# M14_Potis.net
KiCad netlist of a schematic drawn in EAGLE
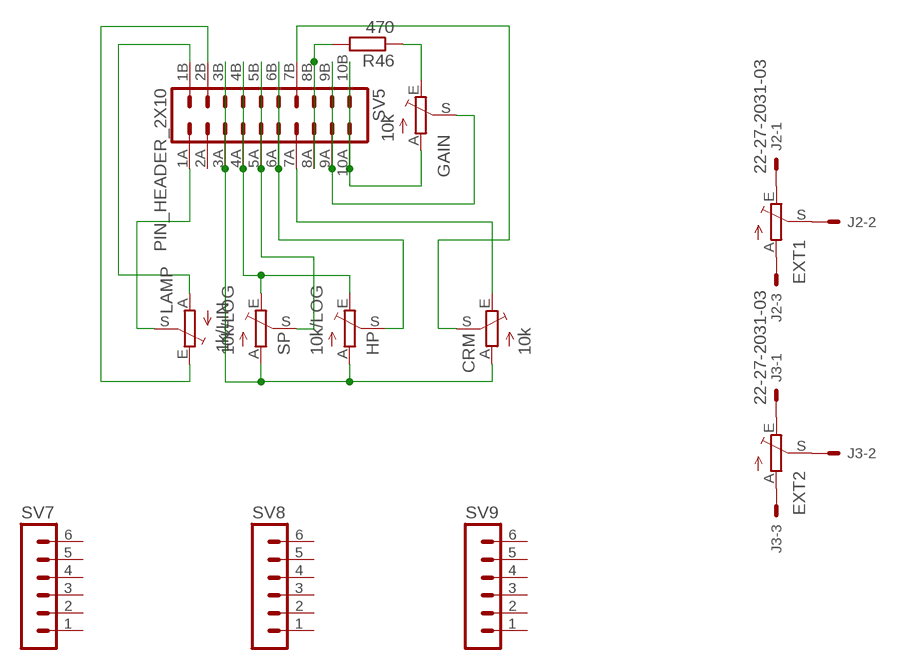
[diagram p0: schematic, sheet 1]

(export (version "E")
  (design (tool "Eeschema 10.0.6"))
  (components
    (comp (ref "CRM")
      (value "10k")
      (footprint "eagle-import:PT-10")
      (libsource (lib "eagle-import") (part "TRIM_EU-PT10"))
    )
    (comp (ref "EXT1")
      (value "TRIM_EU-PT10")
      (footprint "eagle-import:PT-10")
      (libsource (lib "eagle-import") (part "TRIM_EU-PT10"))
    )
    (comp (ref "EXT2")
      (value "TRIM_EU-PT10")
      (footprint "eagle-import:PT-10")
      (libsource (lib "eagle-import") (part "TRIM_EU-PT10"))
    )
    (comp (ref "GAIN")
      (value "10k")
      (footprint "eagle-import:PT-10")
      (libsource (lib "eagle-import") (part "TRIM_EU-PT10"))
    )
    (comp (ref "HP")
      (value "10k/LOG")
      (footprint "eagle-import:POT_NAR")
      (libsource (lib "eagle-import") (part "TRIM_EU-POT_WHOLE"))
    )
    (comp (ref "J2")
      (value "22-27-2031-03")
      (footprint "eagle-import:6410-03")
      (libsource (lib "eagle-import") (part "22-?-0327-2031"))
    )
    (comp (ref "J3")
      (value "22-27-2031-03")
      (footprint "eagle-import:6410-03")
      (libsource (lib "eagle-import") (part "22-?-0327-2031"))
    )
    (comp (ref "LAMP")
      (value "1k/LIN")
      (footprint "eagle-import:POT_NAR")
      (libsource (lib "eagle-import") (part "TRIM_EU-POT_WHOLE"))
    )
    (comp (ref "R46")
      (value "470")
      (footprint "eagle-import:R0805")
      (libsource (lib "eagle-import") (part "R-EU_R0805"))
    )
    (comp (ref "SP")
      (value "10k/LOG")
      (footprint "eagle-import:POT_NAR")
      (libsource (lib "eagle-import") (part "TRIM_EU-POT_WHOLE"))
    )
    (comp (ref "SV5")
      (value "PIN_HEADER_2X10")
      (footprint "eagle-import:PIN_HEADER_2X10SMD")
      (libsource (lib "eagle-import") (part "PIN_HEADER_2X10"))
    )
    (comp (ref "SV7")
      (value "MA06-1")
      (footprint "eagle-import:MA06-1")
      (libsource (lib "eagle-import") (part "MA06-1"))
    )
    (comp (ref "SV8")
      (value "MA06-1")
      (footprint "eagle-import:MA06-1")
      (libsource (lib "eagle-import") (part "MA06-1"))
    )
    (comp (ref "SV9")
      (value "MA06-1")
      (footprint "eagle-import:MA06-1")
      (libsource (lib "eagle-import") (part "MA06-1"))
    )
  )
  (nets
    (net (code "1") (name "Net-(GAIN-PadE)") (class "Default")
      (node (ref "GAIN") (pin "E") (pinfunction "E_E") (pintype "passive"))
      (node (ref "R46") (pin "1") (pinfunction "1_1") (pintype "passive"))
    )
    (net (code "2") (name "Net-(J2A-S)") (class "Default")
      (node (ref "EXT1") (pin "E") (pinfunction "E_E") (pintype "passive"))
      (node (ref "J2") (pin "1") (pinfunction "S_1") (pintype "passive"))
    )
    (net (code "3") (name "Net-(J2B-S)") (class "Default")
      (node (ref "EXT1") (pin "S") (pinfunction "S_S") (pintype "passive"))
      (node (ref "J2") (pin "2") (pinfunction "S_2") (pintype "passive"))
    )
    (net (code "4") (name "Net-(J2C-S)") (class "Default")
      (node (ref "EXT1") (pin "A") (pinfunction "A_A") (pintype "passive"))
      (node (ref "J2") (pin "3") (pinfunction "S_3") (pintype "passive"))
    )
    (net (code "5") (name "Net-(J3A-S)") (class "Default")
      (node (ref "EXT2") (pin "E") (pinfunction "E_E") (pintype "passive"))
      (node (ref "J3") (pin "1") (pinfunction "S_1") (pintype "passive"))
    )
    (net (code "6") (name "Net-(J3B-S)") (class "Default")
      (node (ref "EXT2") (pin "S") (pinfunction "S_S") (pintype "passive"))
      (node (ref "J3") (pin "2") (pinfunction "S_2") (pintype "passive"))
    )
    (net (code "7") (name "Net-(J3C-S)") (class "Default")
      (node (ref "EXT2") (pin "A") (pinfunction "A_A") (pintype "passive"))
      (node (ref "J3") (pin "3") (pinfunction "S_3") (pintype "passive"))
    )
    (net (code "8") (name "Net-(SV5-1)") (class "Default")
      (node (ref "LAMP") (pin "S") (pinfunction "S_S") (pintype "passive"))
      (node (ref "SV5") (pin "1A") (pinfunction "1_1A") (pintype "passive"))
    )
    (net (code "9") (name "Net-(SV5-2)") (class "Default")
      (node (ref "LAMP") (pin "A") (pinfunction "A_A") (pintype "passive"))
      (node (ref "SV5") (pin "1B") (pinfunction "2_1B") (pintype "passive"))
    )
    (net (code "10") (name "Net-(SV5-4)") (class "Default")
      (node (ref "LAMP") (pin "E") (pinfunction "E_E") (pintype "passive"))
      (node (ref "SV5") (pin "2B") (pinfunction "4_2B") (pintype "passive"))
    )
    (net (code "11") (name "Net-(SV5-5)") (class "Default")
      (node (ref "CRM") (pin "A") (pinfunction "A_A") (pintype "passive"))
      (node (ref "HP") (pin "A") (pinfunction "A_A") (pintype "passive"))
      (node (ref "SP") (pin "A") (pinfunction "A_A") (pintype "passive"))
      (node (ref "SV5") (pin "3A") (pinfunction "5_3A") (pintype "passive"))
      (node (ref "SV5") (pin "3B") (pinfunction "6_3B") (pintype "passive"))
    )
    (net (code "12") (name "Net-(SV5-7)") (class "Default")
      (node (ref "HP") (pin "E") (pinfunction "E_E") (pintype "passive"))
      (node (ref "SP") (pin "E") (pinfunction "E_E") (pintype "passive"))
      (node (ref "SV5") (pin "4A") (pinfunction "7_4A") (pintype "passive"))
      (node (ref "SV5") (pin "4B") (pinfunction "8_4B") (pintype "passive"))
    )
    (net (code "13") (name "Net-(SV5-10)") (class "Default")
      (node (ref "SP") (pin "S") (pinfunction "S_S") (pintype "passive"))
      (node (ref "SV5") (pin "5A") (pinfunction "9_5A") (pintype "passive"))
      (node (ref "SV5") (pin "5B") (pinfunction "10_5B") (pintype "passive"))
    )
    (net (code "14") (name "Net-(SV5-11)") (class "Default")
      (node (ref "HP") (pin "S") (pinfunction "S_S") (pintype "passive"))
      (node (ref "SV5") (pin "6A") (pinfunction "11_6A") (pintype "passive"))
      (node (ref "SV5") (pin "6B") (pinfunction "12_6B") (pintype "passive"))
    )
    (net (code "15") (name "Net-(SV5-13)") (class "Default")
      (node (ref "CRM") (pin "E") (pinfunction "E_E") (pintype "passive"))
      (node (ref "SV5") (pin "7A") (pinfunction "13_7A") (pintype "passive"))
    )
    (net (code "16") (name "Net-(SV5-14)") (class "Default")
      (node (ref "CRM") (pin "S") (pinfunction "S_S") (pintype "passive"))
      (node (ref "SV5") (pin "7B") (pinfunction "14_7B") (pintype "passive"))
    )
    (net (code "17") (name "Net-(SV5-15)") (class "Default")
      (node (ref "R46") (pin "2") (pinfunction "2_2") (pintype "passive"))
      (node (ref "SV5") (pin "8A") (pinfunction "15_8A") (pintype "passive"))
      (node (ref "SV5") (pin "8B") (pinfunction "16_8B") (pintype "passive"))
    )
    (net (code "18") (name "Net-(SV5-17)") (class "Default")
      (node (ref "GAIN") (pin "S") (pinfunction "S_S") (pintype "passive"))
      (node (ref "SV5") (pin "9A") (pinfunction "17_9A") (pintype "passive"))
      (node (ref "SV5") (pin "9B") (pinfunction "18_9B") (pintype "passive"))
    )
    (net (code "19") (name "Net-(SV5-19)") (class "Default")
      (node (ref "GAIN") (pin "A") (pinfunction "A_A") (pintype "passive"))
      (node (ref "SV5") (pin "10A") (pinfunction "19_10A") (pintype "passive"))
      (node (ref "SV5") (pin "10B") (pinfunction "20_10B") (pintype "passive"))
    )
    (net (code "20") (name "unconnected-(SV5-3-Pad2A)") (class "Default")
      (node (ref "SV5") (pin "2A") (pinfunction "3_2A") (pintype "passive"))
    )
    (net (code "21") (name "unconnected-(SV7-Pad1)") (class "Default")
      (node (ref "SV7") (pin "1") (pinfunction "1_1") (pintype "passive"))
    )
    (net (code "22") (name "unconnected-(SV7-Pad2)") (class "Default")
      (node (ref "SV7") (pin "2") (pinfunction "2_2") (pintype "passive"))
    )
    (net (code "23") (name "unconnected-(SV7-Pad3)") (class "Default")
      (node (ref "SV7") (pin "3") (pinfunction "3_3") (pintype "passive"))
    )
    (net (code "24") (name "unconnected-(SV7-Pad4)") (class "Default")
      (node (ref "SV7") (pin "4") (pinfunction "4_4") (pintype "passive"))
    )
    (net (code "25") (name "unconnected-(SV7-Pad5)") (class "Default")
      (node (ref "SV7") (pin "5") (pinfunction "5_5") (pintype "passive"))
    )
    (net (code "26") (name "unconnected-(SV7-Pad6)") (class "Default")
      (node (ref "SV7") (pin "6") (pinfunction "6_6") (pintype "passive"))
    )
    (net (code "27") (name "unconnected-(SV8-Pad1)") (class "Default")
      (node (ref "SV8") (pin "1") (pinfunction "1_1") (pintype "passive"))
    )
    (net (code "28") (name "unconnected-(SV8-Pad2)") (class "Default")
      (node (ref "SV8") (pin "2") (pinfunction "2_2") (pintype "passive"))
    )
    (net (code "29") (name "unconnected-(SV8-Pad3)") (class "Default")
      (node (ref "SV8") (pin "3") (pinfunction "3_3") (pintype "passive"))
    )
    (net (code "30") (name "unconnected-(SV8-Pad4)") (class "Default")
      (node (ref "SV8") (pin "4") (pinfunction "4_4") (pintype "passive"))
    )
    (net (code "31") (name "unconnected-(SV8-Pad5)") (class "Default")
      (node (ref "SV8") (pin "5") (pinfunction "5_5") (pintype "passive"))
    )
    (net (code "32") (name "unconnected-(SV8-Pad6)") (class "Default")
      (node (ref "SV8") (pin "6") (pinfunction "6_6") (pintype "passive"))
    )
    (net (code "33") (name "unconnected-(SV9-Pad1)") (class "Default")
      (node (ref "SV9") (pin "1") (pinfunction "1_1") (pintype "passive"))
    )
    (net (code "34") (name "unconnected-(SV9-Pad2)") (class "Default")
      (node (ref "SV9") (pin "2") (pinfunction "2_2") (pintype "passive"))
    )
    (net (code "35") (name "unconnected-(SV9-Pad3)") (class "Default")
      (node (ref "SV9") (pin "3") (pinfunction "3_3") (pintype "passive"))
    )
    (net (code "36") (name "unconnected-(SV9-Pad4)") (class "Default")
      (node (ref "SV9") (pin "4") (pinfunction "4_4") (pintype "passive"))
    )
    (net (code "37") (name "unconnected-(SV9-Pad5)") (class "Default")
      (node (ref "SV9") (pin "5") (pinfunction "5_5") (pintype "passive"))
    )
    (net (code "38") (name "unconnected-(SV9-Pad6)") (class "Default")
      (node (ref "SV9") (pin "6") (pinfunction "6_6") (pintype "passive"))
    )
  )
)
